# Ham-Dip-V2-004.net
KiCad netlist of a schematic drawn in EAGLE
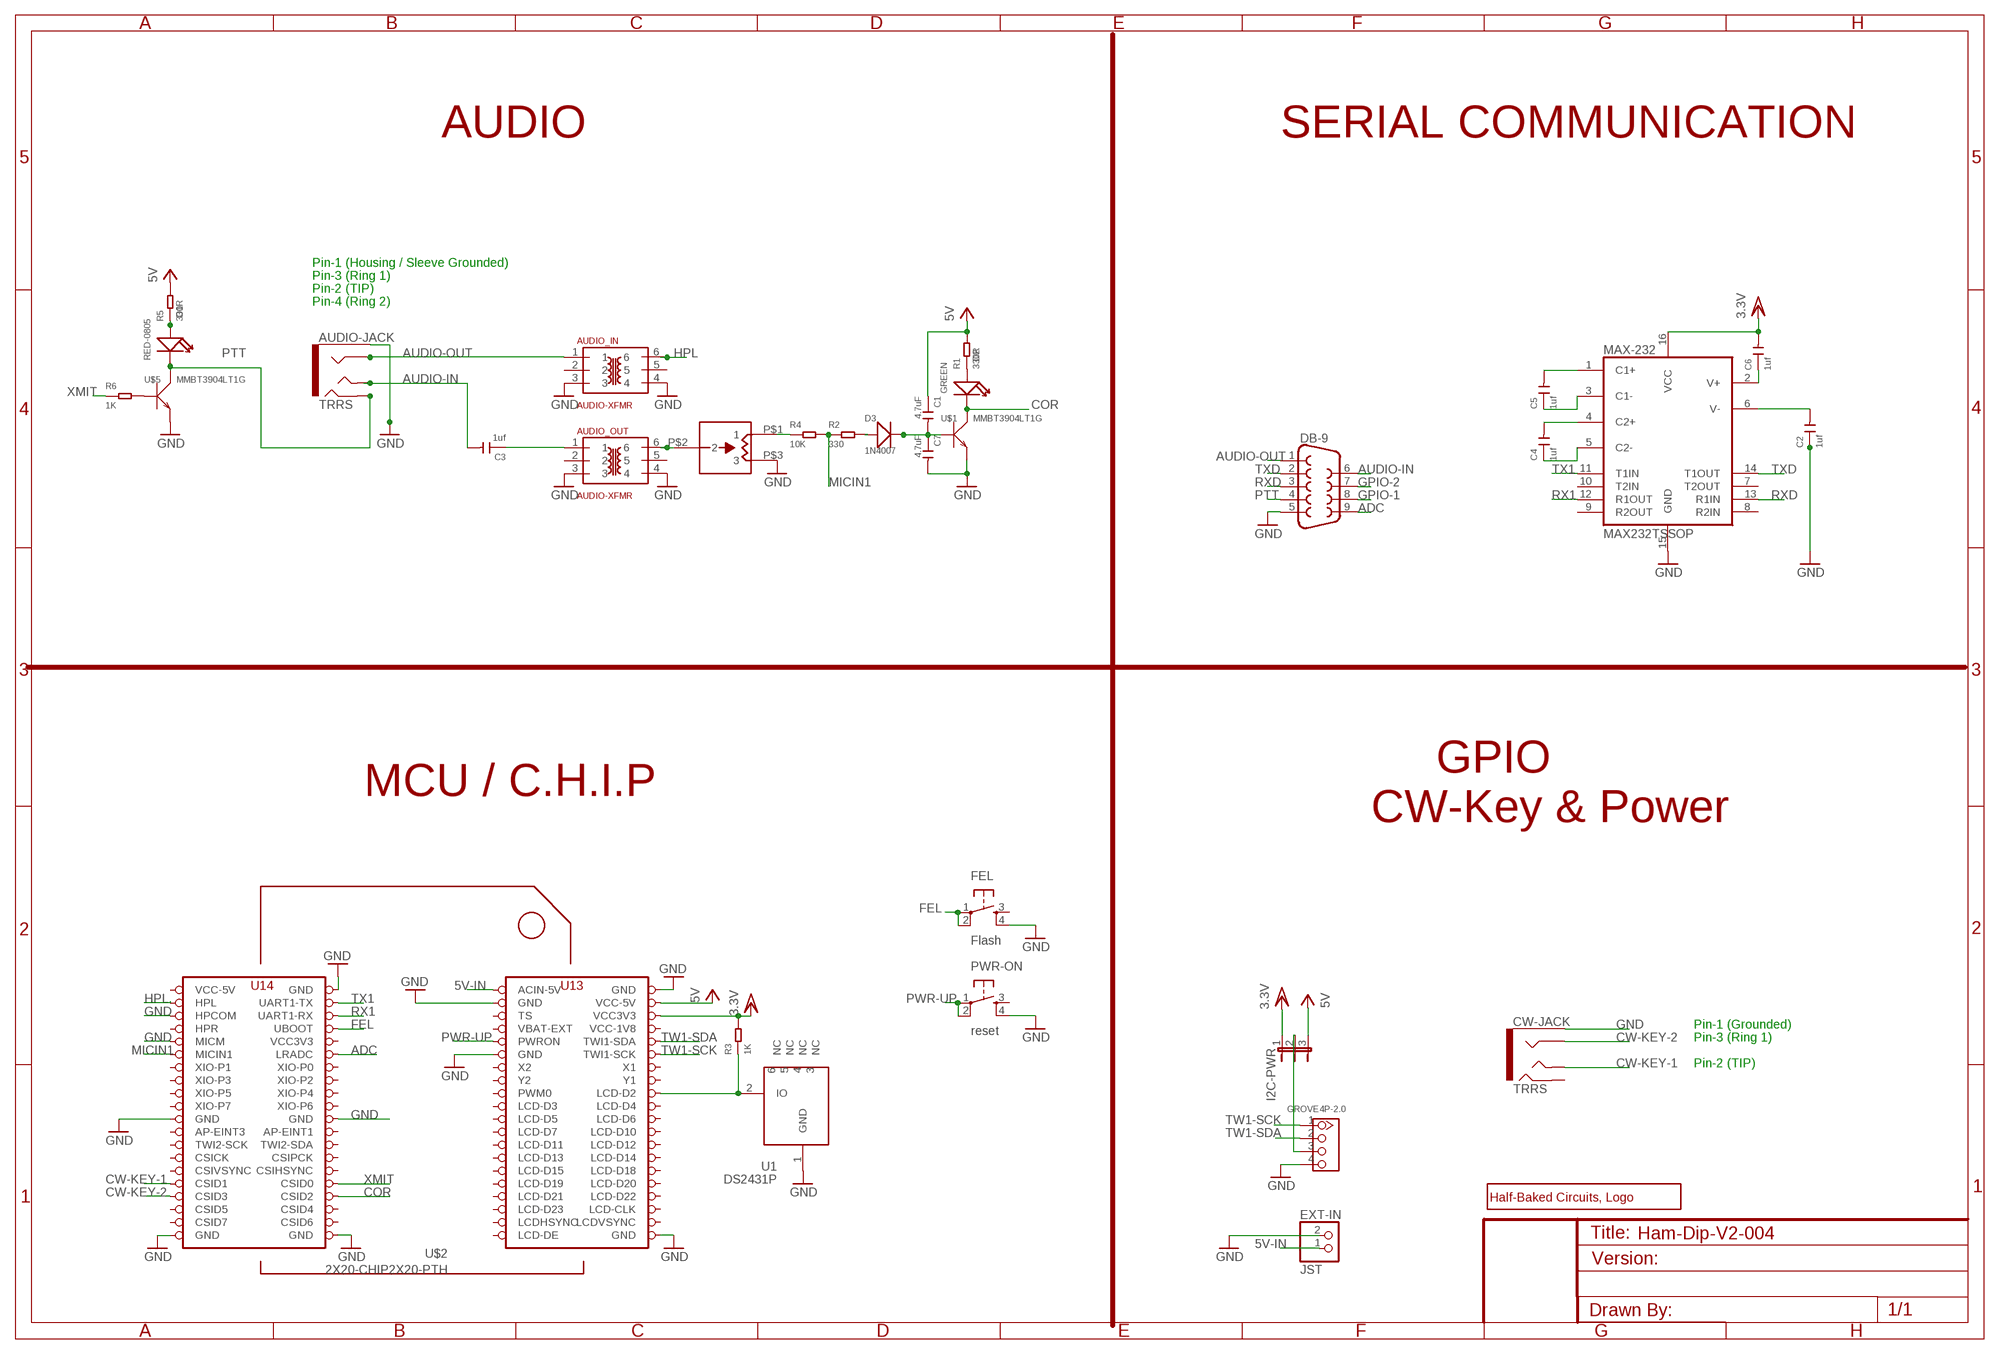
[diagram p0: schematic, sheet 1]

(export (version "E")
  (design (tool "Eeschema 10.0.6"))
  (components
    (comp (ref "AUDIO-JACK")
      (value "TRRS")
      (footprint "eagle-import:AUDIO-JACK-TRRS-SMD")
      (libsource (lib "eagle-import") (part "AUDIO-JACK3"))
    )
    (comp (ref "AUDIO_IN")
      (value "AUDIO-XFMR")
      (footprint "eagle-import:SM-LP-5001")
      (libsource (lib "eagle-import") (part "SM-LP-5001"))
    )
    (comp (ref "AUDIO_OUT")
      (value "AUDIO-XFMR")
      (footprint "eagle-import:SM-LP-5001")
      (libsource (lib "eagle-import") (part "SM-LP-5001"))
    )
    (comp (ref "C1")
      (value "4.7uF")
      (footprint "eagle-import:C0805")
      (fields (field (name "MPN") "CC0805KKX7R8BB105"))
      (libsource (lib "eagle-import") (part "CERAMIC-1UF-25V-10%-X7R(0805)"))
    )
    (comp (ref "C2")
      (value "1uf")
      (footprint "eagle-import:C0805")
      (fields (field (name "MPN") "CC0805KKX7R8BB105"))
      (libsource (lib "eagle-import") (part "CERAMIC-1UF-25V-10%-X7R(0805)"))
    )
    (comp (ref "C3")
      (value "1uf")
      (footprint "eagle-import:C0805")
      (fields (field (name "MPN") "CC0805KKX7R8BB105"))
      (libsource (lib "eagle-import") (part "CERAMIC-1UF-25V-10%-X7R(0805)"))
    )
    (comp (ref "C4")
      (value "1uf")
      (footprint "eagle-import:C0805")
      (fields (field (name "MPN") "CC0805KKX7R8BB105"))
      (libsource (lib "eagle-import") (part "CERAMIC-1UF-25V-10%-X7R(0805)"))
    )
    (comp (ref "C5")
      (value "1uf")
      (footprint "eagle-import:C0805")
      (fields (field (name "MPN") "CC0805KKX7R8BB105"))
      (libsource (lib "eagle-import") (part "CERAMIC-1UF-25V-10%-X7R(0805)"))
    )
    (comp (ref "C6")
      (value "1uf")
      (footprint "eagle-import:C0805")
      (fields (field (name "MPN") "CC0805KKX7R8BB105"))
      (libsource (lib "eagle-import") (part "CERAMIC-1UF-25V-10%-X7R(0805)"))
    )
    (comp (ref "C7")
      (value "4.7uF")
      (footprint "eagle-import:C0805")
      (fields (field (name "MPN") "CC0805KKX7R8BB105"))
      (libsource (lib "eagle-import") (part "CERAMIC-1UF-25V-10%-X7R(0805)"))
    )
    (comp (ref "CW-JACK")
      (value "TRRS")
      (footprint "eagle-import:AUDIO-JACK-TRRS-SMD")
      (libsource (lib "eagle-import") (part "AUDIO-JACK3"))
    )
    (comp (ref "D1")
      (value "RED-0805")
      (footprint "eagle-import:LED-0805")
      (fields (field (name "MPN") "17-215SURC/S530-A2/TR8"))
      (libsource (lib "eagle-import") (part "SMD-LED-CLEAR-RED(0805)"))
    )
    (comp (ref "D2")
      (value "GREEN")
      (footprint "eagle-import:LED-0805")
      (fields (field (name "MPN") "17-215SURC/S530-A2/TR8"))
      (libsource (lib "eagle-import") (part "SMD-LED-CLEAR-RED(0805)"))
    )
    (comp (ref "D3")
      (value "1N4007")
      (footprint "eagle-import:DO-214AC")
      (libsource (lib "eagle-import") (part "DIODE-GEN-PURPOSE-1KV-1A(DO-214AC)"))
    )
    (comp (ref "DB-9")
      (value "DB9FEMALE")
      (footprint "eagle-import:DB9")
      (libsource (lib "eagle-import") (part "DB9FEMALE"))
    )
    (comp (ref "EXT-IN")
      (value "JST")
      (footprint "eagle-import:JST-PH-2-THM")
      (libsource (lib "eagle-import") (part "JST_2PIN-THM"))
    )
    (comp (ref "FEL")
      (value "Flash")
      (footprint "eagle-import:TACTILE_SWITCH_SMD")
      (libsource (lib "eagle-import") (part "TAC_SWITCHSMD"))
    )
    (comp (ref "GROVE")
      (value "4P-2.0")
      (footprint "eagle-import:HW4-2.0")
      (libsource (lib "eagle-import") (part "GROVE-CONNECTOR-DIP(4P-2.0)"))
    )
    (comp (ref "I2C-PWR")
      (value "JP2E")
      (footprint "eagle-import:JP2")
      (libsource (lib "eagle-import") (part "JP2E"))
    )
    (comp (ref "MAX-232")
      (value "MAX232TSSOP")
      (footprint "eagle-import:TSSOP16")
      (libsource (lib "eagle-import") (part "MAX232TSSOP"))
    )
    (comp (ref "MIC-LVL")
      (value "1K")
      (footprint "eagle-import:TC33X")
      (libsource (lib "eagle-import") (part "TC33X"))
    )
    (comp (ref "PWR-ON")
      (value "reset")
      (footprint "eagle-import:TACTILE_SWITCH_SMD")
      (libsource (lib "eagle-import") (part "TAC_SWITCHSMD"))
    )
    (comp (ref "R1")
      (value "330R")
      (footprint "eagle-import:R0805")
      (fields (field (name "MPN") "RC0805JR-07220RL"))
      (libsource (lib "eagle-import") (part "SMD-RES-220R-5%-1/8W(0805)"))
    )
    (comp (ref "R2")
      (value "330")
      (footprint "eagle-import:R0805")
      (fields (field (name "MPN") "RC0805JR-07220RL"))
      (libsource (lib "eagle-import") (part "SMD-RES-220R-5%-1/8W(0805)"))
    )
    (comp (ref "R3")
      (value "1K")
      (footprint "eagle-import:R0805")
      (fields (field (name "MPN") "RC0805JR-07220RL"))
      (libsource (lib "eagle-import") (part "SMD-RES-220R-5%-1/8W(0805)"))
    )
    (comp (ref "R4")
      (value "10K")
      (footprint "eagle-import:R0805")
      (fields (field (name "MPN") "RC0805FR-0710KL"))
      (libsource (lib "eagle-import") (part "SMD-RES-10K-1%-1/8W(0805)"))
    )
    (comp (ref "R5")
      (value "330R")
      (footprint "eagle-import:R0805")
      (fields (field (name "MPN") "RC0805JR-07220RL"))
      (libsource (lib "eagle-import") (part "SMD-RES-220R-5%-1/8W(0805)"))
    )
    (comp (ref "R6")
      (value "1K")
      (footprint "eagle-import:R0805")
      (fields (field (name "MPN") "RC0805JR-07220RL"))
      (libsource (lib "eagle-import") (part "SMD-RES-220R-5%-1/8W(0805)"))
    )
    (comp (ref "U$1")
      (value "MMBT3904LT1G")
      (footprint "eagle-import:SOT-23")
      (libsource (lib "eagle-import") (part "SMD-TRANSISTORS-NPN-40V-200MA-MMBT3904LT1G(SOT-23)"))
    )
    (comp (ref "U$2")
      (value "2X20-CHIP2X20-PTH")
      (footprint "eagle-import:2X20CHIP-TH")
      (fields (field (name "VENDOR_PART_NUMBER") "AWHW40-G-SMD-R (single)"))
      (libsource (lib "eagle-import") (part "2X20-CHIP2X20-PTH-CHIP_A"))
    )
    (comp (ref "U$4")
      (value "HAM-DIP")
      (footprint "eagle-import:HAM-DIP")
      (libsource (lib "eagle-import") (part "HAM-DIP"))
    )
    (comp (ref "U$5")
      (value "MMBT3904LT1G")
      (footprint "eagle-import:SOT-23")
      (libsource (lib "eagle-import") (part "SMD-TRANSISTORS-NPN-40V-200MA-MMBT3904LT1G(SOT-23)"))
    )
    (comp (ref "U1")
      (value "DS2431P")
      (footprint "eagle-import:TSOC6")
      (fields (field (name "MFG") "DIGIKEY") (field (name "VENDOR_PART_NUMBER") "DS2431P+T&R"))
      (libsource (lib "eagle-import") (part "DS2431P"))
    )
  )
  (nets
    (net (code "1") (name "/5V-IN") (class "Default")
      (node (ref "EXT-IN") (pin "1") (pinfunction "2_1") (pintype "passive"))
      (node (ref "U$2") (pin "CHG-IN") (pinfunction "ACIN-5V_CHG-IN") (pintype "passive"))
    )
    (net (code "2") (name "/ADC") (class "Default")
      (node (ref "DB-9") (pin "9") (pinfunction "9_9") (pintype "passive"))
      (node (ref "U$2") (pin "LRADC") (pinfunction "LRADC_LRADC") (pintype "passive"))
    )
    (net (code "3") (name "/AUDIO-IN") (class "Default")
      (node (ref "AUDIO-JACK") (pin "TIP") (pinfunction "TIP_TIP") (pintype "bidirectional"))
      (node (ref "C3") (pin "2") (pinfunction "2_2") (pintype "passive"))
      (node (ref "DB-9") (pin "6") (pinfunction "6_6") (pintype "passive"))
    )
    (net (code "4") (name "/AUDIO-OUT") (class "Default")
      (node (ref "AUDIO-JACK") (pin "RING1") (pinfunction "RING1_RING1") (pintype "bidirectional"))
      (node (ref "AUDIO_IN") (pin "1") (pinfunction "1_1") (pintype "bidirectional"))
      (node (ref "DB-9") (pin "1") (pinfunction "1_1") (pintype "passive"))
    )
    (net (code "5") (name "/COR") (class "Default")
      (node (ref "D2") (pin "-") (pinfunction "-_-") (pintype "passive"))
      (node (ref "U$1") (pin "3") (pinfunction "C_3") (pintype "passive"))
      (node (ref "U$2") (pin "CSID2") (pinfunction "CSID2_CSID2") (pintype "passive"))
    )
    (net (code "6") (name "/CW-KEY-1") (class "Default")
      (node (ref "CW-JACK") (pin "TIP") (pinfunction "TIP_TIP") (pintype "bidirectional"))
      (node (ref "U$2") (pin "CSID1") (pinfunction "CSID1_CSID1") (pintype "passive"))
    )
    (net (code "7") (name "/CW-KEY-2") (class "Default")
      (node (ref "CW-JACK") (pin "RING1") (pinfunction "RING1_RING1") (pintype "bidirectional"))
      (node (ref "U$2") (pin "CSID3") (pinfunction "CSID3_CSID3") (pintype "passive"))
    )
    (net (code "8") (name "/FEL") (class "Default")
      (node (ref "FEL") (pin "1") (pinfunction "1_1") (pintype "passive"))
      (node (ref "FEL") (pin "2") (pinfunction "2_2") (pintype "passive"))
      (node (ref "U$2") (pin "FEL") (pinfunction "UBOOT_FEL") (pintype "passive"))
    )
    (net (code "9") (name "/GPIO-1") (class "Default")
      (node (ref "DB-9") (pin "8") (pinfunction "8_8") (pintype "passive"))
    )
    (net (code "10") (name "/GPIO-2") (class "Default")
      (node (ref "DB-9") (pin "7") (pinfunction "7_7") (pintype "passive"))
    )
    (net (code "11") (name "/HPL") (class "Default")
      (node (ref "AUDIO_IN") (pin "6") (pinfunction "6_6") (pintype "bidirectional"))
      (node (ref "U$2") (pin "HPL") (pinfunction "HPL_HPL") (pintype "passive"))
    )
    (net (code "12") (name "/MICIN1") (class "Default")
      (node (ref "R2") (pin "1") (pinfunction "1_1") (pintype "passive"))
      (node (ref "R4") (pin "2") (pinfunction "2_2") (pintype "passive"))
      (node (ref "U$2") (pin "MICIN1") (pinfunction "MICIN1_MICIN1") (pintype "passive"))
    )
    (net (code "13") (name "/PTT") (class "Default")
      (node (ref "AUDIO-JACK") (pin "RING2") (pinfunction "RING2_RING2") (pintype "bidirectional"))
      (node (ref "D1") (pin "-") (pinfunction "-_-") (pintype "passive"))
      (node (ref "DB-9") (pin "4") (pinfunction "4_4") (pintype "passive"))
      (node (ref "U$5") (pin "3") (pinfunction "C_3") (pintype "passive"))
    )
    (net (code "14") (name "/PWR-UP") (class "Default")
      (node (ref "PWR-ON") (pin "1") (pinfunction "1_1") (pintype "passive"))
      (node (ref "PWR-ON") (pin "2") (pinfunction "2_2") (pintype "passive"))
      (node (ref "U$2") (pin "PWRON") (pinfunction "PWRON_PWRON") (pintype "passive"))
    )
    (net (code "15") (name "/RX1") (class "Default")
      (node (ref "MAX-232") (pin "12") (pinfunction "R1OUT_12") (pintype "output"))
      (node (ref "U$2") (pin "UART1-RX") (pinfunction "UART1-RX_UART1-RX") (pintype "passive"))
    )
    (net (code "16") (name "/RXD") (class "Default")
      (node (ref "DB-9") (pin "3") (pinfunction "3_3") (pintype "passive"))
      (node (ref "MAX-232") (pin "13") (pinfunction "R1IN_13") (pintype "input"))
    )
    (net (code "17") (name "/TW1-SCK") (class "Default")
      (node (ref "GROVE") (pin "1") (pinfunction "1_1") (pintype "bidirectional"))
      (node (ref "U$2") (pin "TWI1-SCK") (pinfunction "TWI1-SCK_TWI1-SCK") (pintype "passive"))
    )
    (net (code "18") (name "/TW1-SDA") (class "Default")
      (node (ref "GROVE") (pin "2") (pinfunction "2_2") (pintype "bidirectional"))
      (node (ref "U$2") (pin "TWI1-SDA") (pinfunction "TWI1-SDA_TWI1-SDA") (pintype "passive"))
    )
    (net (code "19") (name "/TX1") (class "Default")
      (node (ref "MAX-232") (pin "11") (pinfunction "T1IN_11") (pintype "input"))
      (node (ref "U$2") (pin "UART1-TX") (pinfunction "UART1-TX_UART1-TX") (pintype "passive"))
    )
    (net (code "20") (name "/TXD") (class "Default")
      (node (ref "DB-9") (pin "2") (pinfunction "2_2") (pintype "passive"))
      (node (ref "MAX-232") (pin "14") (pinfunction "T1OUT_14") (pintype "output"))
    )
    (net (code "21") (name "/VCC-1V8") (class "Default")
      (node (ref "U$2") (pin "VCC1V8") (pinfunction "VCC-1V8_VCC1V8") (pintype "power_in"))
    )
    (net (code "22") (name "/VCC-5V") (class "Default")
      (node (ref "U$2") (pin "VCC5V@1") (pinfunction "VCC-5V_VCC5V@1") (pintype "power_in"))
    )
    (net (code "23") (name "/VCC3V3") (class "Default")
      (node (ref "U$2") (pin "VCC3V3@1") (pinfunction "VCC3V3_VCC3V3@1") (pintype "power_in"))
    )
    (net (code "24") (name "/XMIT") (class "Default")
      (node (ref "R6") (pin "1") (pinfunction "1_1") (pintype "passive"))
      (node (ref "U$2") (pin "CSID0") (pinfunction "CSID0_CSID0") (pintype "passive"))
    )
    (net (code "25") (name "3.3V") (class "Default")
      (node (ref "C6") (pin "2") (pinfunction "2_2") (pintype "passive"))
      (node (ref "I2C-PWR") (pin "1") (pinfunction "1_1") (pintype "passive"))
      (node (ref "MAX-232") (pin "16") (pinfunction "VCC_16") (pintype "bidirectional"))
      (node (ref "R3") (pin "2") (pinfunction "2_2") (pintype "passive"))
      (node (ref "U$2") (pin "VCC3V3") (pinfunction "VCC3V3_VCC3V3") (pintype "power_in"))
    )
    (net (code "26") (name "5V") (class "Default")
      (node (ref "C1") (pin "1") (pinfunction "1_1") (pintype "passive"))
      (node (ref "I2C-PWR") (pin "3") (pinfunction "3_3") (pintype "passive"))
      (node (ref "R1") (pin "2") (pinfunction "2_2") (pintype "passive"))
      (node (ref "R5") (pin "2") (pinfunction "2_2") (pintype "passive"))
      (node (ref "U$2") (pin "VCC5V@0") (pinfunction "VCC-5V_VCC5V@0") (pintype "power_in"))
    )
    (net (code "27") (name "GND") (class "Default")
      (node (ref "AUDIO-JACK") (pin "EARTH") (pinfunction "EARTH_EARTH") (pintype "bidirectional"))
      (node (ref "AUDIO_IN") (pin "3") (pinfunction "3_3") (pintype "bidirectional"))
      (node (ref "AUDIO_IN") (pin "4") (pinfunction "4_4") (pintype "bidirectional"))
      (node (ref "AUDIO_OUT") (pin "3") (pinfunction "3_3") (pintype "bidirectional"))
      (node (ref "AUDIO_OUT") (pin "4") (pinfunction "4_4") (pintype "bidirectional"))
      (node (ref "C2") (pin "1") (pinfunction "1_1") (pintype "passive"))
      (node (ref "C7") (pin "2") (pinfunction "2_2") (pintype "passive"))
      (node (ref "CW-JACK") (pin "EARTH") (pinfunction "EARTH_EARTH") (pintype "bidirectional"))
      (node (ref "DB-9") (pin "5") (pinfunction "5_5") (pintype "passive"))
      (node (ref "EXT-IN") (pin "2") (pinfunction "1_2") (pintype "passive"))
      (node (ref "FEL") (pin "4") (pinfunction "4_4") (pintype "passive"))
      (node (ref "GROVE") (pin "4") (pinfunction "4_4") (pintype "bidirectional"))
      (node (ref "MAX-232") (pin "15") (pinfunction "GND_15") (pintype "bidirectional"))
      (node (ref "MIC-LVL") (pin "P$3") (pinfunction "3_P$3") (pintype "bidirectional"))
      (node (ref "PWR-ON") (pin "4") (pinfunction "4_4") (pintype "passive"))
      (node (ref "U$1") (pin "2") (pinfunction "E_2") (pintype "passive"))
      (node (ref "U$2") (pin "GND@1") (pinfunction "GND_GND@1") (pintype "power_in"))
      (node (ref "U$2") (pin "GND@10") (pinfunction "GND_GND@10") (pintype "power_in"))
      (node (ref "U$2") (pin "GND@2") (pinfunction "GND_GND@2") (pintype "power_in"))
      (node (ref "U$2") (pin "GND@3") (pinfunction "GND_GND@3") (pintype "power_in"))
      (node (ref "U$2") (pin "GND@4") (pinfunction "GND_GND@4") (pintype "power_in"))
      (node (ref "U$2") (pin "GND@5") (pinfunction "GND_GND@5") (pintype "power_in"))
      (node (ref "U$2") (pin "GND@6") (pinfunction "GND_GND@6") (pintype "power_in"))
      (node (ref "U$2") (pin "GND@7") (pinfunction "GND_GND@7") (pintype "power_in"))
      (node (ref "U$2") (pin "GND@8") (pinfunction "GND_GND@8") (pintype "power_in"))
      (node (ref "U$2") (pin "HPCOM") (pinfunction "HPCOM_HPCOM") (pintype "passive"))
      (node (ref "U$2") (pin "MICM") (pinfunction "MICM_MICM") (pintype "passive"))
      (node (ref "U$5") (pin "2") (pinfunction "E_2") (pintype "passive"))
      (node (ref "U1") (pin "1") (pinfunction "GND_1") (pintype "bidirectional"))
    )
    (net (code "28") (name "Net-(AUDIO_OUT-Pad1)") (class "Default")
      (node (ref "AUDIO_OUT") (pin "1") (pinfunction "1_1") (pintype "bidirectional"))
      (node (ref "C3") (pin "1") (pinfunction "1_1") (pintype "passive"))
    )
    (net (code "29") (name "Net-(D1-Pad+)") (class "Default")
      (node (ref "D1") (pin "+") (pinfunction "+_+") (pintype "passive"))
      (node (ref "R5") (pin "1") (pinfunction "1_1") (pintype "passive"))
    )
    (net (code "30") (name "Net-(D2-Pad+)") (class "Default")
      (node (ref "D2") (pin "+") (pinfunction "+_+") (pintype "passive"))
      (node (ref "R1") (pin "1") (pinfunction "1_1") (pintype "passive"))
    )
    (net (code "31") (name "Net-(D3-+)") (class "Default")
      (node (ref "D3") (pin "1") (pinfunction "+_1") (pintype "passive"))
      (node (ref "R2") (pin "2") (pinfunction "2_2") (pintype "passive"))
    )
    (net (code "32") (name "Net-(D3--)") (class "Default")
      (node (ref "C1") (pin "2") (pinfunction "2_2") (pintype "passive"))
      (node (ref "C7") (pin "1") (pinfunction "1_1") (pintype "passive"))
      (node (ref "D3") (pin "2") (pinfunction "-_2") (pintype "passive"))
      (node (ref "U$1") (pin "1") (pinfunction "B_1") (pintype "passive"))
    )
    (net (code "33") (name "Net-(GROVE-Pad3)") (class "Default")
      (node (ref "GROVE") (pin "3") (pinfunction "3_3") (pintype "bidirectional"))
      (node (ref "I2C-PWR") (pin "2") (pinfunction "2_2") (pintype "passive"))
    )
    (net (code "34") (name "Net-(MAX-232-C1+)") (class "Default")
      (node (ref "C5") (pin "2") (pinfunction "2_2") (pintype "passive"))
      (node (ref "MAX-232") (pin "1") (pinfunction "C1+_1") (pintype "bidirectional"))
    )
    (net (code "35") (name "Net-(MAX-232-C1-)") (class "Default")
      (node (ref "C5") (pin "1") (pinfunction "1_1") (pintype "passive"))
      (node (ref "MAX-232") (pin "3") (pinfunction "C1-_3") (pintype "bidirectional"))
    )
    (net (code "36") (name "Net-(MAX-232-C2+)") (class "Default")
      (node (ref "C4") (pin "2") (pinfunction "2_2") (pintype "passive"))
      (node (ref "MAX-232") (pin "4") (pinfunction "C2+_4") (pintype "bidirectional"))
    )
    (net (code "37") (name "Net-(MAX-232-C2-)") (class "Default")
      (node (ref "C4") (pin "1") (pinfunction "1_1") (pintype "passive"))
      (node (ref "MAX-232") (pin "5") (pinfunction "C2-_5") (pintype "bidirectional"))
    )
    (net (code "38") (name "Net-(MAX-232-V+)") (class "Default")
      (node (ref "C6") (pin "1") (pinfunction "1_1") (pintype "passive"))
      (node (ref "MAX-232") (pin "2") (pinfunction "V+_2") (pintype "bidirectional"))
    )
    (net (code "39") (name "Net-(MAX-232-V-)") (class "Default")
      (node (ref "C2") (pin "2") (pinfunction "2_2") (pintype "passive"))
      (node (ref "MAX-232") (pin "6") (pinfunction "V-_6") (pintype "bidirectional"))
    )
    (net (code "40") (name "Net-(MIC-LVL-1)") (class "Default")
      (node (ref "MIC-LVL") (pin "P$1") (pinfunction "1_P$1") (pintype "bidirectional"))
      (node (ref "R4") (pin "1") (pinfunction "1_1") (pintype "passive"))
    )
    (net (code "41") (name "Net-(MIC-LVL-2)") (class "Default")
      (node (ref "AUDIO_OUT") (pin "6") (pinfunction "6_6") (pintype "bidirectional"))
      (node (ref "MIC-LVL") (pin "P$2") (pinfunction "2_P$2") (pintype "bidirectional"))
    )
    (net (code "42") (name "Net-(U$5-B)") (class "Default")
      (node (ref "R6") (pin "2") (pinfunction "2_2") (pintype "passive"))
      (node (ref "U$5") (pin "1") (pinfunction "B_1") (pintype "passive"))
    )
    (net (code "43") (name "Net-(U1-IO)") (class "Default")
      (node (ref "R3") (pin "1") (pinfunction "1_1") (pintype "passive"))
      (node (ref "U$2") (pin "LCD-D2") (pinfunction "LCD-D2_LCD-D2") (pintype "passive"))
      (node (ref "U1") (pin "2") (pinfunction "IO_2") (pintype "bidirectional"))
    )
    (net (code "44") (name "unconnected-(AUDIO_IN-Pad2)") (class "Default")
      (node (ref "AUDIO_IN") (pin "2") (pinfunction "2_2") (pintype "bidirectional"))
    )
    (net (code "45") (name "unconnected-(AUDIO_IN-Pad5)") (class "Default")
      (node (ref "AUDIO_IN") (pin "5") (pinfunction "5_5") (pintype "bidirectional"))
    )
    (net (code "46") (name "unconnected-(AUDIO_OUT-Pad2)") (class "Default")
      (node (ref "AUDIO_OUT") (pin "2") (pinfunction "2_2") (pintype "bidirectional"))
    )
    (net (code "47") (name "unconnected-(AUDIO_OUT-Pad5)") (class "Default")
      (node (ref "AUDIO_OUT") (pin "5") (pinfunction "5_5") (pintype "bidirectional"))
    )
    (net (code "48") (name "unconnected-(CW-JACK-PadRING2)") (class "Default")
      (node (ref "CW-JACK") (pin "RING2") (pinfunction "RING2_RING2") (pintype "bidirectional"))
    )
    (net (code "49") (name "unconnected-(FEL-Pad3)") (class "Default")
      (node (ref "FEL") (pin "3") (pinfunction "3_3") (pintype "passive"))
    )
    (net (code "50") (name "unconnected-(MAX-232-R2IN-Pad8)") (class "Default")
      (node (ref "MAX-232") (pin "8") (pinfunction "R2IN_8") (pintype "input"))
    )
    (net (code "51") (name "unconnected-(MAX-232-R2OUT-Pad9)") (class "Default")
      (node (ref "MAX-232") (pin "9") (pinfunction "R2OUT_9") (pintype "output"))
    )
    (net (code "52") (name "unconnected-(MAX-232-T2IN-Pad10)") (class "Default")
      (node (ref "MAX-232") (pin "10") (pinfunction "T2IN_10") (pintype "input"))
    )
    (net (code "53") (name "unconnected-(MAX-232-T2OUT-Pad7)") (class "Default")
      (node (ref "MAX-232") (pin "7") (pinfunction "T2OUT_7") (pintype "output"))
    )
    (net (code "54") (name "unconnected-(PWR-ON-Pad3)") (class "Default")
      (node (ref "PWR-ON") (pin "3") (pinfunction "3_3") (pintype "passive"))
    )
    (net (code "55") (name "unconnected-(U$2-LCDHSYNC-PadLCD-HSYNC)") (class "Default")
      (node (ref "U$2") (pin "LCD-HSYNC") (pinfunction "LCDHSYNC_LCD-HSYNC") (pintype "passive"))
    )
    (net (code "56") (name "unconnected-(U$2-LCDVSYNC-PadLCD-VSYNC)") (class "Default")
      (node (ref "U$2") (pin "LCD-VSYNC") (pinfunction "LCDVSYNC_LCD-VSYNC") (pintype "passive"))
    )
    (net (code "57") (name "unconnected-(U$2-PadAP-EINT1)") (class "Default")
      (node (ref "U$2") (pin "AP-EINT1") (pinfunction "AP-EINT1_AP-EINT1") (pintype "passive"))
    )
    (net (code "58") (name "unconnected-(U$2-PadAP-EINT3)") (class "Default")
      (node (ref "U$2") (pin "AP-EINT3") (pinfunction "AP-EINT3_AP-EINT3") (pintype "passive"))
    )
    (net (code "59") (name "unconnected-(U$2-PadCSICK)") (class "Default")
      (node (ref "U$2") (pin "CSICK") (pinfunction "CSICK_CSICK") (pintype "passive"))
    )
    (net (code "60") (name "unconnected-(U$2-PadCSID4)") (class "Default")
      (node (ref "U$2") (pin "CSID4") (pinfunction "CSID4_CSID4") (pintype "passive"))
    )
    (net (code "61") (name "unconnected-(U$2-PadCSID5)") (class "Default")
      (node (ref "U$2") (pin "CSID5") (pinfunction "CSID5_CSID5") (pintype "passive"))
    )
    (net (code "62") (name "unconnected-(U$2-PadCSID6)") (class "Default")
      (node (ref "U$2") (pin "CSID6") (pinfunction "CSID6_CSID6") (pintype "passive"))
    )
    (net (code "63") (name "unconnected-(U$2-PadCSID7)") (class "Default")
      (node (ref "U$2") (pin "CSID7") (pinfunction "CSID7_CSID7") (pintype "passive"))
    )
    (net (code "64") (name "unconnected-(U$2-PadCSIHSYNC)") (class "Default")
      (node (ref "U$2") (pin "CSIHSYNC") (pinfunction "CSIHSYNC_CSIHSYNC") (pintype "passive"))
    )
    (net (code "65") (name "unconnected-(U$2-PadCSIPCK)") (class "Default")
      (node (ref "U$2") (pin "CSIPCK") (pinfunction "CSIPCK_CSIPCK") (pintype "passive"))
    )
    (net (code "66") (name "unconnected-(U$2-PadCSIVSYNC)") (class "Default")
      (node (ref "U$2") (pin "CSIVSYNC") (pinfunction "CSIVSYNC_CSIVSYNC") (pintype "passive"))
    )
    (net (code "67") (name "unconnected-(U$2-PadHPR)") (class "Default")
      (node (ref "U$2") (pin "HPR") (pinfunction "HPR_HPR") (pintype "passive"))
    )
    (net (code "68") (name "unconnected-(U$2-PadLCD-CLK)") (class "Default")
      (node (ref "U$2") (pin "LCD-CLK") (pinfunction "LCD-CLK_LCD-CLK") (pintype "passive"))
    )
    (net (code "69") (name "unconnected-(U$2-PadLCD-D3)") (class "Default")
      (node (ref "U$2") (pin "LCD-D3") (pinfunction "LCD-D3_LCD-D3") (pintype "passive"))
    )
    (net (code "70") (name "unconnected-(U$2-PadLCD-D4)") (class "Default")
      (node (ref "U$2") (pin "LCD-D4") (pinfunction "LCD-D4_LCD-D4") (pintype "passive"))
    )
    (net (code "71") (name "unconnected-(U$2-PadLCD-D5)") (class "Default")
      (node (ref "U$2") (pin "LCD-D5") (pinfunction "LCD-D5_LCD-D5") (pintype "passive"))
    )
    (net (code "72") (name "unconnected-(U$2-PadLCD-D6)") (class "Default")
      (node (ref "U$2") (pin "LCD-D6") (pinfunction "LCD-D6_LCD-D6") (pintype "passive"))
    )
    (net (code "73") (name "unconnected-(U$2-PadLCD-D7)") (class "Default")
      (node (ref "U$2") (pin "LCD-D7") (pinfunction "LCD-D7_LCD-D7") (pintype "passive"))
    )
    (net (code "74") (name "unconnected-(U$2-PadLCD-D10)") (class "Default")
      (node (ref "U$2") (pin "LCD-D10") (pinfunction "LCD-D10_LCD-D10") (pintype "passive"))
    )
    (net (code "75") (name "unconnected-(U$2-PadLCD-D11)") (class "Default")
      (node (ref "U$2") (pin "LCD-D11") (pinfunction "LCD-D11_LCD-D11") (pintype "passive"))
    )
    (net (code "76") (name "unconnected-(U$2-PadLCD-D12)") (class "Default")
      (node (ref "U$2") (pin "LCD-D12") (pinfunction "LCD-D12_LCD-D12") (pintype "passive"))
    )
    (net (code "77") (name "unconnected-(U$2-PadLCD-D13)") (class "Default")
      (node (ref "U$2") (pin "LCD-D13") (pinfunction "LCD-D13_LCD-D13") (pintype "passive"))
    )
    (net (code "78") (name "unconnected-(U$2-PadLCD-D14)") (class "Default")
      (node (ref "U$2") (pin "LCD-D14") (pinfunction "LCD-D14_LCD-D14") (pintype "passive"))
    )
    (net (code "79") (name "unconnected-(U$2-PadLCD-D15)") (class "Default")
      (node (ref "U$2") (pin "LCD-D15") (pinfunction "LCD-D15_LCD-D15") (pintype "passive"))
    )
    (net (code "80") (name "unconnected-(U$2-PadLCD-D18)") (class "Default")
      (node (ref "U$2") (pin "LCD-D18") (pinfunction "LCD-D18_LCD-D18") (pintype "passive"))
    )
    (net (code "81") (name "unconnected-(U$2-PadLCD-D19)") (class "Default")
      (node (ref "U$2") (pin "LCD-D19") (pinfunction "LCD-D19_LCD-D19") (pintype "passive"))
    )
    (net (code "82") (name "unconnected-(U$2-PadLCD-D20)") (class "Default")
      (node (ref "U$2") (pin "LCD-D20") (pinfunction "LCD-D20_LCD-D20") (pintype "passive"))
    )
    (net (code "83") (name "unconnected-(U$2-PadLCD-D21)") (class "Default")
      (node (ref "U$2") (pin "LCD-D21") (pinfunction "LCD-D21_LCD-D21") (pintype "passive"))
    )
    (net (code "84") (name "unconnected-(U$2-PadLCD-D22)") (class "Default")
      (node (ref "U$2") (pin "LCD-D22") (pinfunction "LCD-D22_LCD-D22") (pintype "passive"))
    )
    (net (code "85") (name "unconnected-(U$2-PadLCD-D23)") (class "Default")
      (node (ref "U$2") (pin "LCD-D23") (pinfunction "LCD-D23_LCD-D23") (pintype "passive"))
    )
    (net (code "86") (name "unconnected-(U$2-PadLCD-DE)") (class "Default")
      (node (ref "U$2") (pin "LCD-DE") (pinfunction "LCD-DE_LCD-DE") (pintype "passive"))
    )
    (net (code "87") (name "unconnected-(U$2-PadPWM0)") (class "Default")
      (node (ref "U$2") (pin "PWM0") (pinfunction "PWM0_PWM0") (pintype "passive"))
    )
    (net (code "88") (name "unconnected-(U$2-PadTS)") (class "Default")
      (node (ref "U$2") (pin "TS") (pinfunction "TS_TS") (pintype "passive"))
    )
    (net (code "89") (name "unconnected-(U$2-PadTWI2-SCK)") (class "Default")
      (node (ref "U$2") (pin "TWI2-SCK") (pinfunction "TWI2-SCK_TWI2-SCK") (pintype "passive"))
    )
    (net (code "90") (name "unconnected-(U$2-PadTWI2-SDA)") (class "Default")
      (node (ref "U$2") (pin "TWI2-SDA") (pinfunction "TWI2-SDA_TWI2-SDA") (pintype "passive"))
    )
    (net (code "91") (name "unconnected-(U$2-PadX1)") (class "Default")
      (node (ref "U$2") (pin "X1") (pinfunction "X1_X1") (pintype "passive"))
    )
    (net (code "92") (name "unconnected-(U$2-PadX2)") (class "Default")
      (node (ref "U$2") (pin "X2") (pinfunction "X2_X2") (pintype "passive"))
    )
    (net (code "93") (name "unconnected-(U$2-PadXIO-P0)") (class "Default")
      (node (ref "U$2") (pin "XIO-P0") (pinfunction "XIO-P0_XIO-P0") (pintype "passive"))
    )
    (net (code "94") (name "unconnected-(U$2-PadXIO-P1)") (class "Default")
      (node (ref "U$2") (pin "XIO-P1") (pinfunction "XIO-P1_XIO-P1") (pintype "passive"))
    )
    (net (code "95") (name "unconnected-(U$2-PadXIO-P2)") (class "Default")
      (node (ref "U$2") (pin "XIO-P2") (pinfunction "XIO-P2_XIO-P2") (pintype "passive"))
    )
    (net (code "96") (name "unconnected-(U$2-PadXIO-P3)") (class "Default")
      (node (ref "U$2") (pin "XIO-P3") (pinfunction "XIO-P3_XIO-P3") (pintype "passive"))
    )
    (net (code "97") (name "unconnected-(U$2-PadXIO-P4)") (class "Default")
      (node (ref "U$2") (pin "XIO-P4") (pinfunction "XIO-P4_XIO-P4") (pintype "passive"))
    )
    (net (code "98") (name "unconnected-(U$2-PadXIO-P5)") (class "Default")
      (node (ref "U$2") (pin "XIO-P5") (pinfunction "XIO-P5_XIO-P5") (pintype "passive"))
    )
    (net (code "99") (name "unconnected-(U$2-PadXIO-P6)") (class "Default")
      (node (ref "U$2") (pin "XIO-P6") (pinfunction "XIO-P6_XIO-P6") (pintype "passive"))
    )
    (net (code "100") (name "unconnected-(U$2-PadXIO-P7)") (class "Default")
      (node (ref "U$2") (pin "XIO-P7") (pinfunction "XIO-P7_XIO-P7") (pintype "passive"))
    )
    (net (code "101") (name "unconnected-(U$2-PadY1)") (class "Default")
      (node (ref "U$2") (pin "Y1") (pinfunction "Y1_Y1") (pintype "passive"))
    )
    (net (code "102") (name "unconnected-(U$2-PadY2)") (class "Default")
      (node (ref "U$2") (pin "Y2") (pinfunction "Y2_Y2") (pintype "passive"))
    )
    (net (code "103") (name "unconnected-(U$2-VBAT-EXT-PadBAT)") (class "Default")
      (node (ref "U$2") (pin "BAT") (pinfunction "VBAT-EXT_BAT") (pintype "passive"))
    )
    (net (code "104") (name "unconnected-(U1-NC-Pad3)") (class "Default")
      (node (ref "U1") (pin "3") (pinfunction "NC_3") (pintype "bidirectional"))
    )
    (net (code "105") (name "unconnected-(U1-NC-Pad4)") (class "Default")
      (node (ref "U1") (pin "4") (pinfunction "NC_4") (pintype "bidirectional"))
    )
    (net (code "106") (name "unconnected-(U1-NC-Pad5)") (class "Default")
      (node (ref "U1") (pin "5") (pinfunction "NC_5") (pintype "bidirectional"))
    )
    (net (code "107") (name "unconnected-(U1-NC-Pad6)") (class "Default")
      (node (ref "U1") (pin "6") (pinfunction "NC_6") (pintype "bidirectional"))
    )
  )
)
